# MCU.net
KiCad netlist of a schematic drawn in Altium Designer
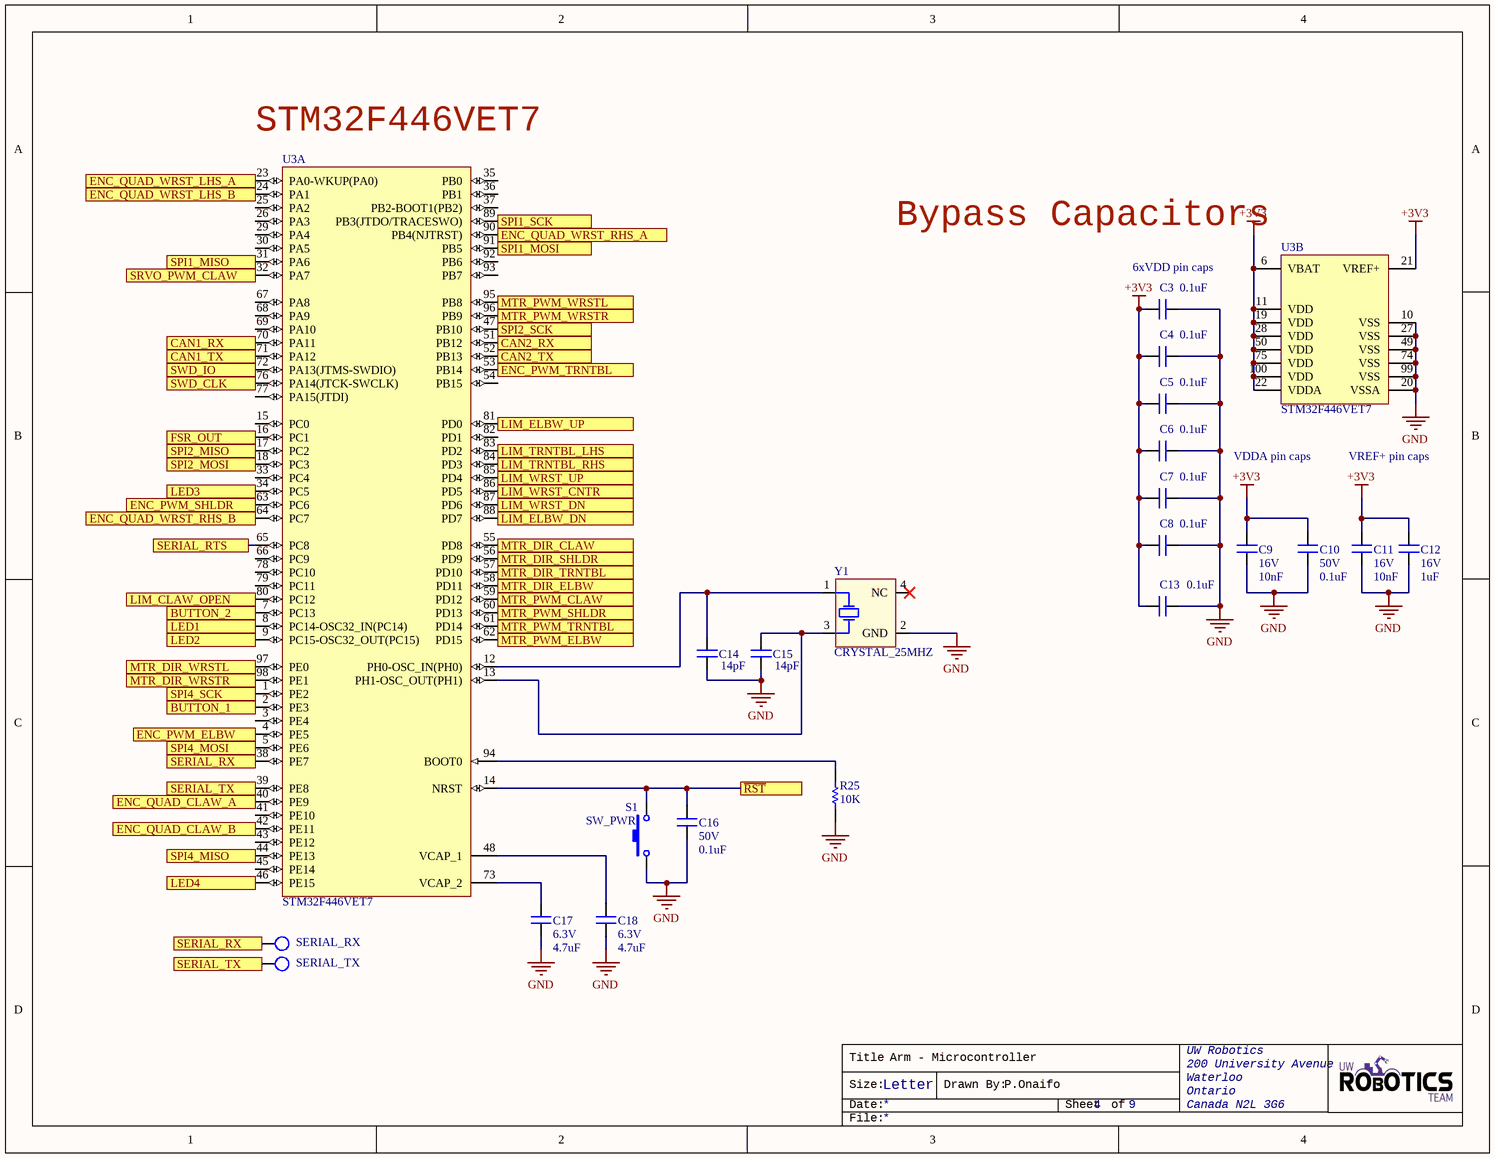
[diagram p0: MCU.SchDoc]

(export (version "E")
  (design (tool "Eeschema 10.0.6"))
  (components
    (comp (ref "C3")
      (value "0.1uF")
      (footprint "CAPC0603(1608)55_N")
      (description "CAP CER 0.1UF 50V X7R 0603")
      (fields (field (name "MPN") "CC0603KRX7R9BB104") (field (name "MANUFACTURER") "Yageo"))
      (libsource (lib "UWRT_Schematic_Library_2020") (part "CAP_0.1uF_50V_0603"))
    )
    (comp (ref "C4")
      (value "0.1uF")
      (footprint "CAPC0603(1608)55_N")
      (description "CAP CER 0.1UF 50V X7R 0603")
      (fields (field (name "MPN") "CC0603KRX7R9BB104") (field (name "MANUFACTURER") "Yageo"))
      (libsource (lib "UWRT_Schematic_Library_2020") (part "CAP_0.1uF_50V_0603"))
    )
    (comp (ref "C5")
      (value "0.1uF")
      (footprint "CAPC0603(1608)55_N")
      (description "CAP CER 0.1UF 50V X7R 0603")
      (fields (field (name "MPN") "CC0603KRX7R9BB104") (field (name "MANUFACTURER") "Yageo"))
      (libsource (lib "UWRT_Schematic_Library_2020") (part "CAP_0.1uF_50V_0603"))
    )
    (comp (ref "C6")
      (value "0.1uF")
      (footprint "CAPC0603(1608)55_N")
      (description "CAP CER 0.1UF 50V X7R 0603")
      (fields (field (name "MPN") "CC0603KRX7R9BB104") (field (name "MANUFACTURER") "Yageo"))
      (libsource (lib "UWRT_Schematic_Library_2020") (part "CAP_0.1uF_50V_0603"))
    )
    (comp (ref "C7")
      (value "0.1uF")
      (footprint "CAPC0603(1608)55_N")
      (description "CAP CER 0.1UF 50V X7R 0603")
      (fields (field (name "MPN") "CC0603KRX7R9BB104") (field (name "MANUFACTURER") "Yageo"))
      (libsource (lib "UWRT_Schematic_Library_2020") (part "CAP_0.1uF_50V_0603"))
    )
    (comp (ref "C8")
      (value "0.1uF")
      (footprint "CAPC0603(1608)55_N")
      (description "CAP CER 0.1UF 50V X7R 0603")
      (fields (field (name "MPN") "CC0603KRX7R9BB104") (field (name "MANUFACTURER") "Yageo"))
      (libsource (lib "UWRT_Schematic_Library_2020") (part "CAP_0.1uF_50V_0603"))
    )
    (comp (ref "C9")
      (value "10nF")
      (footprint "CAPC0603(1608)55_N")
      (description "CAP CER 10000PF 16V X7R 0603")
      (fields
        (field (name "MPN") "CC0603KRX7R7BB103")
        (field (name "MANUFACTURER") "Yageo")
        (field (name "VOLTAGE RATING") "16V")
      )
      (libsource (lib "UWRT_Schematic_Library_2020") (part "CAP_10nF_0603"))
    )
    (comp (ref "C10")
      (value "0.1uF")
      (footprint "CAPC0603(1608)55_N")
      (description "CAP CER 0.1UF 50V X7R 0603")
      (fields
        (field (name "MPN") "CC0603KRX7R9BB104")
        (field (name "MANUFACTURER") "Yageo")
        (field (name "VOLTAGE RATING") "50V")
      )
      (libsource (lib "UWRT_Schematic_Library_2020") (part "CAP_0.1uF_50V_0603"))
    )
    (comp (ref "C11")
      (value "10nF")
      (footprint "CAPC0603(1608)55_N")
      (description "CAP CER 10000PF 16V X7R 0603")
      (fields
        (field (name "MPN") "CC0603KRX7R7BB103")
        (field (name "MANUFACTURER") "Yageo")
        (field (name "VOLTAGE RATING") "16V")
      )
      (libsource (lib "UWRT_Schematic_Library_2020") (part "CAP_10nF_0603"))
    )
    (comp (ref "C12")
      (value "1uF")
      (footprint "CAPC0603(1608)55_N")
      (description "CAP CER 1UF 16V Y5V 0603")
      (fields
        (field (name "MPN") "CC0603ZRY5V7BB105")
        (field (name "MANUFACTURER") "Yageo")
        (field (name "VOLTAGE RATING") "16V")
      )
      (libsource (lib "UWRT_Schematic_Library_2020") (part "CAP_1uF_16V_0603"))
    )
    (comp (ref "C13")
      (value "0.1uF")
      (footprint "CAPC0603(1608)55_N")
      (description "CAP CER 0.1UF 50V X7R 0603")
      (fields (field (name "MPN") "CC0603KRX7R9BB104") (field (name "MANUFACTURER") "Yageo"))
      (libsource (lib "UWRT_Schematic_Library_2020") (part "CAP_0.1uF_50V_0603"))
    )
    (comp (ref "C14")
      (value "14pF")
      (description "CAP CER 14PF 50V C0G/NP0 0603")
      (fields (field (name "TOLERANCE") "5%") (field (name "Comment") "CAP_14pF_50V_0603"))
      (libsource (lib "UWRT_Schematic_Library_2020") (part "CAP_14pF_50V_0603"))
    )
    (comp (ref "C15")
      (value "14pF")
      (description "CAP CER 14PF 50V C0G/NP0 0603")
      (fields (field (name "TOLERANCE") "5%") (field (name "Comment") "CAP_14pF_50V_0603"))
      (libsource (lib "UWRT_Schematic_Library_2020") (part "CAP_14pF_50V_0603"))
    )
    (comp (ref "C16")
      (value "0.1uF")
      (footprint "CAPC0603(1608)55_N")
      (description "CAP CER 0.1UF 50V X7R 0603")
      (fields
        (field (name "MPN") "CC0603KRX7R9BB104")
        (field (name "MANUFACTURER") "Yageo")
        (field (name "VOLTAGE RATING") "50V")
      )
      (libsource (lib "UWRT_Schematic_Library_2020") (part "CAP_0.1uF_50V_0603"))
    )
    (comp (ref "C17")
      (value "4.7uF")
      (footprint "CAPC0603(1608)55_N")
      (description "CAP CER 4.7UF 6.3V X5R 0603")
      (fields
        (field (name "MPN") "CC0603KRX5R5BB475")
        (field (name "MANUFACTURER") "Yageo")
        (field (name "VOLTAGE RATING") "6.3V")
      )
      (libsource (lib "UWRT_Schematic_Library_2020") (part "CAP_4.7uF_0603"))
    )
    (comp (ref "C18")
      (value "4.7uF")
      (footprint "CAPC0603(1608)55_N")
      (description "CAP CER 4.7UF 6.3V X5R 0603")
      (fields
        (field (name "MPN") "CC0603KRX5R5BB475")
        (field (name "MANUFACTURER") "Yageo")
        (field (name "VOLTAGE RATING") "6.3V")
      )
      (libsource (lib "UWRT_Schematic_Library_2020") (part "CAP_4.7uF_0603"))
    )
    (comp (ref "R25")
      (value "10K")
      (footprint "RESC0603(1608)_N")
      (description "RES SMD 10K OHM 5% 1/10W 0603")
      (fields (field (name "MANUFACTURER") "Yageo") (field (name "MPN") "RC0603JR-0710KL"))
      (libsource (lib "UWRT_Schematic_Library_2020") (part "RES_10K_0603"))
    )
    (comp (ref "S1")
      (value "SW_PWR")
      (footprint "PTS830GM140")
      (description "Power Switch (Red)")
      (fields (field (name "MPN") "PTS830GM140 SMTR LFS") (field (name "MANUFACTURER") "C&K"))
      (libsource (lib "UWRT_Schematic_Library_2020") (part "SW_PWR"))
    )
    (comp (ref "SERIAL_RX")
      (value "TESTPOINT_LOOP")
      (footprint "TESTPOINT_LOOP")
      (description "Loop testpoint through-hole pad")
      (fields (field (name "MANUFACTURER") "Keystone Electronics"))
      (libsource (lib "UWRT_Schematic_Library_2020") (part "TESTPOINT_LOOP"))
    )
    (comp (ref "SERIAL_TX")
      (value "TESTPOINT_LOOP")
      (footprint "TESTPOINT_LOOP")
      (description "Loop testpoint through-hole pad")
      (fields (field (name "MANUFACTURER") "Keystone Electronics"))
      (libsource (lib "UWRT_Schematic_Library_2020") (part "TESTPOINT_LOOP"))
    )
    (comp (ref "U3")
      (value "STM32F446VET7")
      (footprint "STM-LQFP100_L")
      (libsource (lib "Altium Content Vault") (part "MC-ARM-STM32F446-LQFP100"))
    )
    (comp (ref "Y1")
      (value "CRYSTAL_25MHZ")
      (description "CRYSTAL 25.0000MHZ 12PF SMD")
      (libsource (lib "UWRT_Schematic_Library_2020") (part "CRYSTAL_25MHZ"))
    )
  )
  (nets
    (net (code "1") (name "+3V3") (class "Default")
      (node (ref "C10") (pin "2") (pinfunction "2_2") (pintype "passive"))
      (node (ref "C11") (pin "1") (pinfunction "1_1") (pintype "passive"))
      (node (ref "C12") (pin "2") (pinfunction "2_2") (pintype "passive"))
      (node (ref "C13") (pin "1") (pinfunction "1_1") (pintype "passive"))
      (node (ref "C3") (pin "1") (pinfunction "1_1") (pintype "passive"))
      (node (ref "C4") (pin "1") (pinfunction "1_1") (pintype "passive"))
      (node (ref "C5") (pin "1") (pinfunction "1_1") (pintype "passive"))
      (node (ref "C6") (pin "1") (pinfunction "1_1") (pintype "passive"))
      (node (ref "C7") (pin "1") (pinfunction "1_1") (pintype "passive"))
      (node (ref "C8") (pin "1") (pinfunction "1_1") (pintype "passive"))
      (node (ref "C9") (pin "2") (pinfunction "2_2") (pintype "passive"))
      (node (ref "U3") (pin "100") (pinfunction "VDD_100") (pintype "power_in"))
      (node (ref "U3") (pin "11") (pinfunction "VDD_11") (pintype "power_in"))
      (node (ref "U3") (pin "19") (pinfunction "VDD_19") (pintype "power_in"))
      (node (ref "U3") (pin "21") (pinfunction "VREF+_21") (pintype "power_in"))
      (node (ref "U3") (pin "22") (pinfunction "VDDA_22") (pintype "power_in"))
      (node (ref "U3") (pin "28") (pinfunction "VDD_28") (pintype "power_in"))
      (node (ref "U3") (pin "50") (pinfunction "VDD_50") (pintype "power_in"))
      (node (ref "U3") (pin "6") (pinfunction "VBAT_6") (pintype "power_in"))
      (node (ref "U3") (pin "75") (pinfunction "VDD_75") (pintype "power_in"))
    )
    (net (code "2") (name "/BUTTON_1") (class "Default")
      (node (ref "U3") (pin "2") (pinfunction "PE3_2") (pintype "bidirectional"))
    )
    (net (code "3") (name "/BUTTON_2") (class "Default")
      (node (ref "U3") (pin "7") (pinfunction "PC13_7") (pintype "bidirectional"))
    )
    (net (code "4") (name "/CAN1_RX") (class "Default")
      (node (ref "U3") (pin "70") (pinfunction "PA11_70") (pintype "bidirectional"))
    )
    (net (code "5") (name "/CAN1_TX") (class "Default")
      (node (ref "U3") (pin "71") (pinfunction "PA12_71") (pintype "bidirectional"))
    )
    (net (code "6") (name "/CAN2_RX") (class "Default")
      (node (ref "U3") (pin "51") (pinfunction "PB12_51") (pintype "bidirectional"))
    )
    (net (code "7") (name "/CAN2_TX") (class "Default")
      (node (ref "U3") (pin "52") (pinfunction "PB13_52") (pintype "bidirectional"))
    )
    (net (code "8") (name "/ENC_PWM_ELBW") (class "Default")
      (node (ref "U3") (pin "4") (pinfunction "PE5_4") (pintype "bidirectional"))
    )
    (net (code "9") (name "/ENC_PWM_SHLDR") (class "Default")
      (node (ref "U3") (pin "63") (pinfunction "PC6_63") (pintype "bidirectional"))
    )
    (net (code "10") (name "/ENC_PWM_TRNTBL") (class "Default")
      (node (ref "U3") (pin "53") (pinfunction "PB14_53") (pintype "bidirectional"))
    )
    (net (code "11") (name "/ENC_QUAD_CLAW_A") (class "Default")
      (node (ref "U3") (pin "40") (pinfunction "PE9_40") (pintype "bidirectional"))
    )
    (net (code "12") (name "/ENC_QUAD_CLAW_B") (class "Default")
      (node (ref "U3") (pin "42") (pinfunction "PE11_42") (pintype "bidirectional"))
    )
    (net (code "13") (name "/ENC_QUAD_WRST_LHS_A") (class "Default")
      (node (ref "U3") (pin "23") (pinfunction "PA0-WKUP(PA0)_23") (pintype "bidirectional"))
    )
    (net (code "14") (name "/ENC_QUAD_WRST_LHS_B") (class "Default")
      (node (ref "U3") (pin "24") (pinfunction "PA1_24") (pintype "bidirectional"))
    )
    (net (code "15") (name "/ENC_QUAD_WRST_RHS_A") (class "Default")
      (node (ref "U3") (pin "90") (pinfunction "PB4(NJTRST)_90") (pintype "bidirectional"))
    )
    (net (code "16") (name "/ENC_QUAD_WRST_RHS_B") (class "Default")
      (node (ref "U3") (pin "64") (pinfunction "PC7_64") (pintype "bidirectional"))
    )
    (net (code "17") (name "/FSR_OUT") (class "Default")
      (node (ref "U3") (pin "16") (pinfunction "PC1_16") (pintype "bidirectional"))
    )
    (net (code "18") (name "/LED1") (class "Default")
      (node (ref "U3") (pin "8") (pinfunction "PC14-OSC32_IN(PC14)_8") (pintype "bidirectional"))
    )
    (net (code "19") (name "/LED2") (class "Default")
      (node (ref "U3") (pin "9") (pinfunction "PC15-OSC32_OUT(PC15)_9") (pintype "bidirectional"))
    )
    (net (code "20") (name "/LED3") (class "Default")
      (node (ref "U3") (pin "34") (pinfunction "PC5_34") (pintype "bidirectional"))
    )
    (net (code "21") (name "/LED4") (class "Default")
      (node (ref "U3") (pin "46") (pinfunction "PE15_46") (pintype "bidirectional"))
    )
    (net (code "22") (name "/LIM_CLAW_OPEN") (class "Default")
      (node (ref "U3") (pin "80") (pinfunction "PC12_80") (pintype "bidirectional"))
    )
    (net (code "23") (name "/LIM_ELBW_DN") (class "Default")
      (node (ref "U3") (pin "88") (pinfunction "PD7_88") (pintype "bidirectional"))
    )
    (net (code "24") (name "/LIM_ELBW_UP") (class "Default")
      (node (ref "U3") (pin "81") (pinfunction "PD0_81") (pintype "bidirectional"))
    )
    (net (code "25") (name "/LIM_TRNTBL_LHS") (class "Default")
      (node (ref "U3") (pin "83") (pinfunction "PD2_83") (pintype "bidirectional"))
    )
    (net (code "26") (name "/LIM_TRNTBL_RHS") (class "Default")
      (node (ref "U3") (pin "84") (pinfunction "PD3_84") (pintype "bidirectional"))
    )
    (net (code "27") (name "/LIM_WRST_CNTR") (class "Default")
      (node (ref "U3") (pin "86") (pinfunction "PD5_86") (pintype "bidirectional"))
    )
    (net (code "28") (name "/LIM_WRST_DN") (class "Default")
      (node (ref "U3") (pin "87") (pinfunction "PD6_87") (pintype "bidirectional"))
    )
    (net (code "29") (name "/LIM_WRST_UP") (class "Default")
      (node (ref "U3") (pin "85") (pinfunction "PD4_85") (pintype "bidirectional"))
    )
    (net (code "30") (name "/MTR_DIR_CLAW") (class "Default")
      (node (ref "U3") (pin "55") (pinfunction "PD8_55") (pintype "bidirectional"))
    )
    (net (code "31") (name "/MTR_DIR_ELBW") (class "Default")
      (node (ref "U3") (pin "58") (pinfunction "PD11_58") (pintype "bidirectional"))
    )
    (net (code "32") (name "/MTR_DIR_SHLDR") (class "Default")
      (node (ref "U3") (pin "56") (pinfunction "PD9_56") (pintype "bidirectional"))
    )
    (net (code "33") (name "/MTR_DIR_TRNTBL") (class "Default")
      (node (ref "U3") (pin "57") (pinfunction "PD10_57") (pintype "bidirectional"))
    )
    (net (code "34") (name "/MTR_DIR_WRSTL") (class "Default")
      (node (ref "U3") (pin "97") (pinfunction "PE0_97") (pintype "bidirectional"))
    )
    (net (code "35") (name "/MTR_DIR_WRSTR") (class "Default")
      (node (ref "U3") (pin "98") (pinfunction "PE1_98") (pintype "bidirectional"))
    )
    (net (code "36") (name "/MTR_PWM_CLAW") (class "Default")
      (node (ref "U3") (pin "59") (pinfunction "PD12_59") (pintype "bidirectional"))
    )
    (net (code "37") (name "/MTR_PWM_ELBW") (class "Default")
      (node (ref "U3") (pin "62") (pinfunction "PD15_62") (pintype "bidirectional"))
    )
    (net (code "38") (name "/MTR_PWM_SHLDR") (class "Default")
      (node (ref "U3") (pin "60") (pinfunction "PD13_60") (pintype "bidirectional"))
    )
    (net (code "39") (name "/MTR_PWM_TRNTBL") (class "Default")
      (node (ref "U3") (pin "61") (pinfunction "PD14_61") (pintype "bidirectional"))
    )
    (net (code "40") (name "/MTR_PWM_WRSTL") (class "Default")
      (node (ref "U3") (pin "95") (pinfunction "PB8_95") (pintype "bidirectional"))
    )
    (net (code "41") (name "/MTR_PWM_WRSTR") (class "Default")
      (node (ref "U3") (pin "96") (pinfunction "PB9_96") (pintype "bidirectional"))
    )
    (net (code "42") (name "/SERIAL_RTS") (class "Default")
      (node (ref "U3") (pin "65") (pinfunction "PC8_65") (pintype "bidirectional"))
    )
    (net (code "43") (name "/SERIAL_RX") (class "Default")
      (node (ref "SERIAL_RX") (pin "1") (pintype "passive"))
      (node (ref "U3") (pin "38") (pinfunction "PE7_38") (pintype "bidirectional"))
    )
    (net (code "44") (name "/SERIAL_TX") (class "Default")
      (node (ref "SERIAL_TX") (pin "1") (pintype "passive"))
      (node (ref "U3") (pin "39") (pinfunction "PE8_39") (pintype "bidirectional"))
    )
    (net (code "45") (name "/SPI1_MISO") (class "Default")
      (node (ref "U3") (pin "31") (pinfunction "PA6_31") (pintype "bidirectional"))
    )
    (net (code "46") (name "/SPI1_MOSI") (class "Default")
      (node (ref "U3") (pin "91") (pinfunction "PB5_91") (pintype "bidirectional"))
    )
    (net (code "47") (name "/SPI1_SCK") (class "Default")
      (node (ref "U3") (pin "89") (pinfunction "PB3(JTDO/TRACESWO)_89") (pintype "bidirectional"))
    )
    (net (code "48") (name "/SPI2_MISO") (class "Default")
      (node (ref "U3") (pin "17") (pinfunction "PC2_17") (pintype "bidirectional"))
    )
    (net (code "49") (name "/SPI2_MOSI") (class "Default")
      (node (ref "U3") (pin "18") (pinfunction "PC3_18") (pintype "bidirectional"))
    )
    (net (code "50") (name "/SPI2_SCK") (class "Default")
      (node (ref "U3") (pin "47") (pinfunction "PB10_47") (pintype "bidirectional"))
    )
    (net (code "51") (name "/SPI4_MISO") (class "Default")
      (node (ref "U3") (pin "44") (pinfunction "PE13_44") (pintype "bidirectional"))
    )
    (net (code "52") (name "/SPI4_MOSI") (class "Default")
      (node (ref "U3") (pin "5") (pinfunction "PE6_5") (pintype "bidirectional"))
    )
    (net (code "53") (name "/SPI4_SCK") (class "Default")
      (node (ref "U3") (pin "1") (pinfunction "PE2_1") (pintype "bidirectional"))
    )
    (net (code "54") (name "/SRVO_PWM_CLAW") (class "Default")
      (node (ref "U3") (pin "32") (pinfunction "PA7_32") (pintype "bidirectional"))
    )
    (net (code "55") (name "/SWD_CLK") (class "Default")
      (node (ref "U3") (pin "76") (pinfunction "PA14(JTCK-SWCLK)_76") (pintype "bidirectional"))
    )
    (net (code "56") (name "/SWD_IO") (class "Default")
      (node (ref "U3") (pin "72") (pinfunction "PA13(JTMS-SWDIO)_72") (pintype "bidirectional"))
    )
    (net (code "57") (name "/~{RST}") (class "Default")
      (node (ref "C16") (pin "2") (pinfunction "2_2") (pintype "passive"))
      (node (ref "S1") (pin "2") (pinfunction "2_2") (pintype "passive"))
      (node (ref "U3") (pin "14") (pinfunction "NRST_14") (pintype "bidirectional"))
    )
    (net (code "58") (name "GND") (class "Default")
      (node (ref "C10") (pin "1") (pinfunction "1_1") (pintype "passive"))
      (node (ref "C11") (pin "2") (pinfunction "2_2") (pintype "passive"))
      (node (ref "C12") (pin "1") (pinfunction "1_1") (pintype "passive"))
      (node (ref "C13") (pin "2") (pinfunction "2_2") (pintype "passive"))
      (node (ref "C14") (pin "1") (pinfunction "1_1") (pintype "passive"))
      (node (ref "C15") (pin "1") (pinfunction "1_1") (pintype "passive"))
      (node (ref "C16") (pin "1") (pinfunction "1_1") (pintype "passive"))
      (node (ref "C17") (pin "1") (pinfunction "1_1") (pintype "passive"))
      (node (ref "C18") (pin "1") (pinfunction "1_1") (pintype "passive"))
      (node (ref "C3") (pin "2") (pinfunction "2_2") (pintype "passive"))
      (node (ref "C4") (pin "2") (pinfunction "2_2") (pintype "passive"))
      (node (ref "C5") (pin "2") (pinfunction "2_2") (pintype "passive"))
      (node (ref "C6") (pin "2") (pinfunction "2_2") (pintype "passive"))
      (node (ref "C7") (pin "2") (pinfunction "2_2") (pintype "passive"))
      (node (ref "C8") (pin "2") (pinfunction "2_2") (pintype "passive"))
      (node (ref "C9") (pin "1") (pinfunction "1_1") (pintype "passive"))
      (node (ref "R25") (pin "2") (pinfunction "2_2") (pintype "passive"))
      (node (ref "S1") (pin "1") (pinfunction "1_1") (pintype "passive"))
      (node (ref "U3") (pin "10") (pinfunction "VSS_10") (pintype "power_in"))
      (node (ref "U3") (pin "20") (pinfunction "VSSA_20") (pintype "power_in"))
      (node (ref "U3") (pin "27") (pinfunction "VSS_27") (pintype "power_in"))
      (node (ref "U3") (pin "49") (pinfunction "VSS_49") (pintype "power_in"))
      (node (ref "U3") (pin "74") (pinfunction "VSS_74") (pintype "power_in"))
      (node (ref "U3") (pin "99") (pinfunction "VSS_99") (pintype "power_in"))
      (node (ref "Y1") (pin "2") (pinfunction "GND_2") (pintype "power_in"))
    )
    (net (code "59") (name "Net-(U3A-BOOT0)") (class "Default")
      (node (ref "R25") (pin "1") (pinfunction "1_1") (pintype "passive"))
      (node (ref "U3") (pin "94") (pinfunction "BOOT0_94") (pintype "input"))
    )
    (net (code "60") (name "Net-(U3A-PH0-OSC_IN(PH0))") (class "Default")
      (node (ref "C14") (pin "2") (pinfunction "2_2") (pintype "passive"))
      (node (ref "U3") (pin "12") (pinfunction "PH0-OSC_IN(PH0)_12") (pintype "bidirectional"))
      (node (ref "Y1") (pin "1") (pinfunction "HOT_1") (pintype "passive"))
    )
    (net (code "61") (name "Net-(U3A-PH1-OSC_OUT(PH1))") (class "Default")
      (node (ref "C15") (pin "2") (pinfunction "2_2") (pintype "passive"))
      (node (ref "U3") (pin "13") (pinfunction "PH1-OSC_OUT(PH1)_13") (pintype "bidirectional"))
      (node (ref "Y1") (pin "3") (pinfunction "HOT_3") (pintype "passive"))
    )
    (net (code "62") (name "Net-(U3A-VCAP_1)") (class "Default")
      (node (ref "C18") (pin "2") (pinfunction "2_2") (pintype "passive"))
      (node (ref "U3") (pin "48") (pinfunction "VCAP_1_48") (pintype "passive"))
    )
    (net (code "63") (name "Net-(U3A-VCAP_2)") (class "Default")
      (node (ref "C17") (pin "2") (pinfunction "2_2") (pintype "passive"))
      (node (ref "U3") (pin "73") (pinfunction "VCAP_2_73") (pintype "passive"))
    )
    (net (code "64") (name "unconnected-(U3A-PA2-Pad25)") (class "Default")
      (node (ref "U3") (pin "25") (pinfunction "PA2_25") (pintype "bidirectional"))
    )
    (net (code "65") (name "unconnected-(U3A-PA3-Pad26)") (class "Default")
      (node (ref "U3") (pin "26") (pinfunction "PA3_26") (pintype "bidirectional"))
    )
    (net (code "66") (name "unconnected-(U3A-PA4-Pad29)") (class "Default")
      (node (ref "U3") (pin "29") (pinfunction "PA4_29") (pintype "bidirectional"))
    )
    (net (code "67") (name "unconnected-(U3A-PA5-Pad30)") (class "Default")
      (node (ref "U3") (pin "30") (pinfunction "PA5_30") (pintype "bidirectional"))
    )
    (net (code "68") (name "unconnected-(U3A-PA8-Pad67)") (class "Default")
      (node (ref "U3") (pin "67") (pinfunction "PA8_67") (pintype "bidirectional"))
    )
    (net (code "69") (name "unconnected-(U3A-PA9-Pad68)") (class "Default")
      (node (ref "U3") (pin "68") (pinfunction "PA9_68") (pintype "bidirectional"))
    )
    (net (code "70") (name "unconnected-(U3A-PA10-Pad69)") (class "Default")
      (node (ref "U3") (pin "69") (pinfunction "PA10_69") (pintype "bidirectional"))
    )
    (net (code "71") (name "unconnected-(U3A-PA15(JTDI)-Pad77)") (class "Default")
      (node (ref "U3") (pin "77") (pinfunction "PA15(JTDI)_77") (pintype "bidirectional"))
    )
    (net (code "72") (name "unconnected-(U3A-PB0-Pad35)") (class "Default")
      (node (ref "U3") (pin "35") (pinfunction "PB0_35") (pintype "bidirectional"))
    )
    (net (code "73") (name "unconnected-(U3A-PB1-Pad36)") (class "Default")
      (node (ref "U3") (pin "36") (pinfunction "PB1_36") (pintype "bidirectional"))
    )
    (net (code "74") (name "unconnected-(U3A-PB2-BOOT1(PB2)-Pad37)") (class "Default")
      (node (ref "U3") (pin "37") (pinfunction "PB2-BOOT1(PB2)_37") (pintype "bidirectional"))
    )
    (net (code "75") (name "unconnected-(U3A-PB6-Pad92)") (class "Default")
      (node (ref "U3") (pin "92") (pinfunction "PB6_92") (pintype "bidirectional"))
    )
    (net (code "76") (name "unconnected-(U3A-PB7-Pad93)") (class "Default")
      (node (ref "U3") (pin "93") (pinfunction "PB7_93") (pintype "bidirectional"))
    )
    (net (code "77") (name "unconnected-(U3A-PB15-Pad54)") (class "Default")
      (node (ref "U3") (pin "54") (pinfunction "PB15_54") (pintype "bidirectional"))
    )
    (net (code "78") (name "unconnected-(U3A-PC0-Pad15)") (class "Default")
      (node (ref "U3") (pin "15") (pinfunction "PC0_15") (pintype "bidirectional"))
    )
    (net (code "79") (name "unconnected-(U3A-PC4-Pad33)") (class "Default")
      (node (ref "U3") (pin "33") (pinfunction "PC4_33") (pintype "bidirectional"))
    )
    (net (code "80") (name "unconnected-(U3A-PC9-Pad66)") (class "Default")
      (node (ref "U3") (pin "66") (pinfunction "PC9_66") (pintype "bidirectional"))
    )
    (net (code "81") (name "unconnected-(U3A-PC10-Pad78)") (class "Default")
      (node (ref "U3") (pin "78") (pinfunction "PC10_78") (pintype "bidirectional"))
    )
    (net (code "82") (name "unconnected-(U3A-PC11-Pad79)") (class "Default")
      (node (ref "U3") (pin "79") (pinfunction "PC11_79") (pintype "bidirectional"))
    )
    (net (code "83") (name "unconnected-(U3A-PD1-Pad82)") (class "Default")
      (node (ref "U3") (pin "82") (pinfunction "PD1_82") (pintype "bidirectional"))
    )
    (net (code "84") (name "unconnected-(U3A-PE4-Pad3)") (class "Default")
      (node (ref "U3") (pin "3") (pinfunction "PE4_3") (pintype "bidirectional"))
    )
    (net (code "85") (name "unconnected-(U3A-PE10-Pad41)") (class "Default")
      (node (ref "U3") (pin "41") (pinfunction "PE10_41") (pintype "bidirectional"))
    )
    (net (code "86") (name "unconnected-(U3A-PE12-Pad43)") (class "Default")
      (node (ref "U3") (pin "43") (pinfunction "PE12_43") (pintype "bidirectional"))
    )
    (net (code "87") (name "unconnected-(U3A-PE14-Pad45)") (class "Default")
      (node (ref "U3") (pin "45") (pinfunction "PE14_45") (pintype "bidirectional"))
    )
    (net (code "88") (name "unconnected-(Y1-NC-Pad4)") (class "Default")
      (node (ref "Y1") (pin "4") (pinfunction "NC_4") (pintype "passive+no_connect"))
    )
  )
)
